# ethernet_chip_board.net
KiCad netlist of a schematic drawn in EAGLE
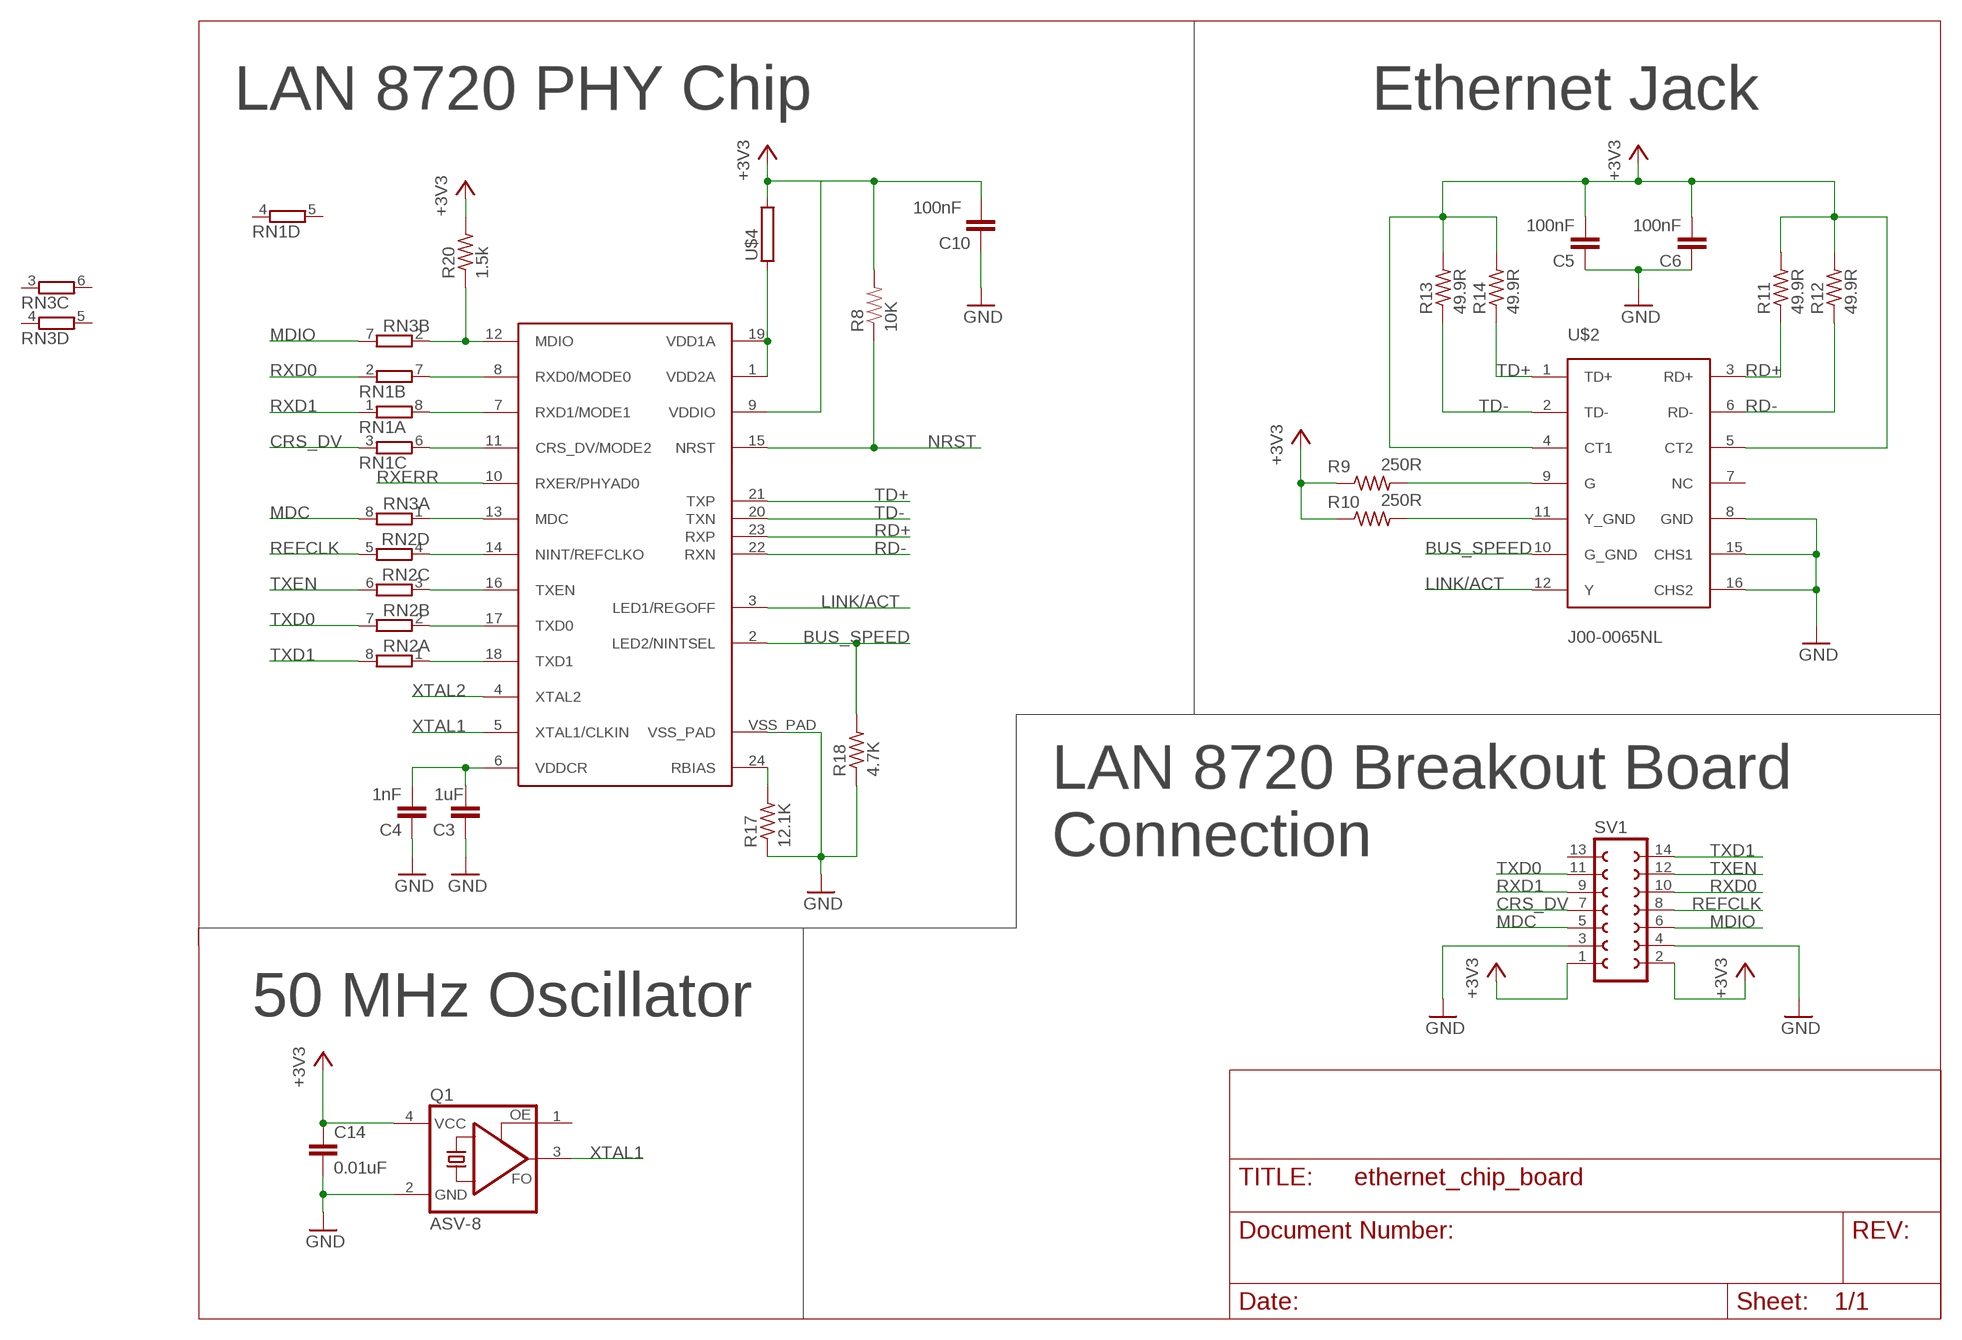
[diagram p0: schematic, sheet 1]

(export (version "E")
  (design (tool "Eeschema 10.0.6"))
  (components
    (comp (ref "C3")
      (value "1uF")
      (footprint "eagle-import:C0603")
      (libsource (lib "eagle-import") (part "CC0603"))
    )
    (comp (ref "C4")
      (value "1nF")
      (footprint "eagle-import:C0603")
      (libsource (lib "eagle-import") (part "CC0603"))
    )
    (comp (ref "C5")
      (value "100nF")
      (footprint "eagle-import:C0603")
      (libsource (lib "eagle-import") (part "CC0603"))
    )
    (comp (ref "C6")
      (value "100nF")
      (footprint "eagle-import:C0603")
      (libsource (lib "eagle-import") (part "CC0603"))
    )
    (comp (ref "C10")
      (value "100nF")
      (footprint "eagle-import:C0603")
      (libsource (lib "eagle-import") (part "CC0603"))
    )
    (comp (ref "C14")
      (value "0.01uF")
      (footprint "eagle-import:C0603")
      (libsource (lib "eagle-import") (part "C-EUC0603"))
    )
    (comp (ref "Q1")
      (value "ASV-8")
      (footprint "eagle-import:ASF")
      (libsource (lib "eagle-import") (part "ASF"))
    )
    (comp (ref "R8")
      (value "10K")
      (footprint "eagle-import:0603-RES")
      (libsource (lib "eagle-import") (part "RESISTOR0603-RES"))
    )
    (comp (ref "R9")
      (value "250R")
      (footprint "eagle-import:R0603")
      (libsource (lib "eagle-import") (part "R-US_R0603"))
    )
    (comp (ref "R10")
      (value "250R")
      (footprint "eagle-import:R0603")
      (libsource (lib "eagle-import") (part "R-US_R0603"))
    )
    (comp (ref "R11")
      (value "49.9R")
      (footprint "eagle-import:R0603")
      (libsource (lib "eagle-import") (part "R-US_R0603"))
    )
    (comp (ref "R12")
      (value "49.9R")
      (footprint "eagle-import:R0603")
      (libsource (lib "eagle-import") (part "R-US_R0603"))
    )
    (comp (ref "R13")
      (value "49.9R")
      (footprint "eagle-import:R0603")
      (libsource (lib "eagle-import") (part "R-US_R0603"))
    )
    (comp (ref "R14")
      (value "49.9R")
      (footprint "eagle-import:R0603")
      (libsource (lib "eagle-import") (part "R-US_R0603"))
    )
    (comp (ref "R17")
      (value "12.1K")
      (footprint "eagle-import:R0603")
      (libsource (lib "eagle-import") (part "R-US_R0603"))
    )
    (comp (ref "R18")
      (value "4.7K")
      (footprint "eagle-import:R0603")
      (libsource (lib "eagle-import") (part "R-US_R0603"))
    )
    (comp (ref "R20")
      (value "1.5k")
      (footprint "eagle-import:R0603")
      (libsource (lib "eagle-import") (part "R-US_R0603"))
    )
    (comp (ref "RN1")
      (value "4R-NCAY16")
      (footprint "eagle-import:CAY16")
      (libsource (lib "eagle-import") (part "4R-NCAY16"))
    )
    (comp (ref "RN2")
      (value "4R-NCAY16")
      (footprint "eagle-import:CAY16")
      (libsource (lib "eagle-import") (part "4R-NCAY16"))
    )
    (comp (ref "RN3")
      (value "4R-NCAY16")
      (footprint "eagle-import:CAY16")
      (libsource (lib "eagle-import") (part "4R-NCAY16"))
    )
    (comp (ref "SV1")
      (value "FE07-2")
      (footprint "eagle-import:FE07-2")
      (libsource (lib "eagle-import") (part "FE07-2"))
    )
    (comp (ref "U$1")
      (value "LAN8720LAN8720")
      (footprint "eagle-import:24-QFN")
      (libsource (lib "eagle-import") (part "LAN8720LAN8720"))
    )
    (comp (ref "U$2")
      (value "J00-0065NL")
      (footprint "eagle-import:J00-0065NL")
      (libsource (lib "eagle-import") (part "J00-0065NL"))
    )
    (comp (ref "U$4")
      (value "553-2382-1-ND")
      (footprint "eagle-import:0603")
      (libsource (lib "eagle-import") (part "553-2382-1-ND"))
    )
  )
  (nets
    (net (code "1") (name "+3V3") (class "Default")
      (node (ref "C10") (pin "2") (pinfunction "2_2") (pintype "passive"))
      (node (ref "C14") (pin "1") (pinfunction "1_1") (pintype "passive"))
      (node (ref "C5") (pin "2") (pinfunction "2_2") (pintype "passive"))
      (node (ref "C6") (pin "2") (pinfunction "2_2") (pintype "passive"))
      (node (ref "Q1") (pin "4") (pinfunction "VCC_4") (pintype "power_in"))
      (node (ref "R10") (pin "1") (pinfunction "1_1") (pintype "passive"))
      (node (ref "R11") (pin "2") (pinfunction "2_2") (pintype "passive"))
      (node (ref "R12") (pin "2") (pinfunction "2_2") (pintype "passive"))
      (node (ref "R13") (pin "2") (pinfunction "2_2") (pintype "passive"))
      (node (ref "R14") (pin "2") (pinfunction "2_2") (pintype "passive"))
      (node (ref "R20") (pin "2") (pinfunction "2_2") (pintype "passive"))
      (node (ref "R8") (pin "2") (pinfunction "2_2") (pintype "passive"))
      (node (ref "R9") (pin "1") (pinfunction "1_1") (pintype "passive"))
      (node (ref "SV1") (pin "1") (pinfunction "1_1") (pintype "passive"))
      (node (ref "SV1") (pin "2") (pinfunction "2_2") (pintype "passive"))
      (node (ref "U$1") (pin "9") (pinfunction "VDDIO_9") (pintype "bidirectional"))
      (node (ref "U$2") (pin "4") (pinfunction "CT1_4") (pintype "bidirectional"))
      (node (ref "U$2") (pin "5") (pinfunction "CT2_5") (pintype "bidirectional"))
      (node (ref "U$4") (pin "2") (pinfunction "2_2") (pintype "passive"))
    )
    (net (code "2") (name "/BUS_SPEED") (class "Default")
      (node (ref "R18") (pin "2") (pinfunction "2_2") (pintype "passive"))
      (node (ref "U$1") (pin "2") (pinfunction "LED2/NINTSEL_2") (pintype "bidirectional"))
      (node (ref "U$2") (pin "10") (pinfunction "G_GND_10") (pintype "bidirectional"))
    )
    (net (code "3") (name "/CRS_DV") (class "Default")
      (node (ref "RN1") (pin "3") (pinfunction "1_3") (pintype "passive"))
      (node (ref "SV1") (pin "7") (pinfunction "7_7") (pintype "passive"))
    )
    (net (code "4") (name "/LINK{slash}ACT") (class "Default")
      (node (ref "U$1") (pin "3") (pinfunction "LED1/REGOFF_3") (pintype "bidirectional"))
      (node (ref "U$2") (pin "12") (pinfunction "Y_12") (pintype "bidirectional"))
    )
    (net (code "5") (name "/MDC") (class "Default")
      (node (ref "RN3") (pin "8") (pinfunction "2_8") (pintype "passive"))
      (node (ref "SV1") (pin "5") (pinfunction "5_5") (pintype "passive"))
    )
    (net (code "6") (name "/MDIO") (class "Default")
      (node (ref "RN3") (pin "7") (pinfunction "2_7") (pintype "passive"))
      (node (ref "SV1") (pin "6") (pinfunction "6_6") (pintype "passive"))
    )
    (net (code "7") (name "/NRST") (class "Default")
      (node (ref "R8") (pin "1") (pinfunction "1_1") (pintype "passive"))
      (node (ref "U$1") (pin "15") (pinfunction "NRST_15") (pintype "bidirectional"))
    )
    (net (code "8") (name "/RD+") (class "Default")
      (node (ref "R11") (pin "1") (pinfunction "1_1") (pintype "passive"))
      (node (ref "U$1") (pin "23") (pinfunction "RXP_23") (pintype "bidirectional"))
      (node (ref "U$2") (pin "3") (pinfunction "RD+_3") (pintype "bidirectional"))
    )
    (net (code "9") (name "/RD-") (class "Default")
      (node (ref "R12") (pin "1") (pinfunction "1_1") (pintype "passive"))
      (node (ref "U$1") (pin "22") (pinfunction "RXN_22") (pintype "bidirectional"))
      (node (ref "U$2") (pin "6") (pinfunction "RD-_6") (pintype "bidirectional"))
    )
    (net (code "10") (name "/REFCLK") (class "Default")
      (node (ref "RN2") (pin "5") (pinfunction "2_5") (pintype "passive"))
      (node (ref "SV1") (pin "8") (pinfunction "8_8") (pintype "passive"))
    )
    (net (code "11") (name "/RXD0") (class "Default")
      (node (ref "RN1") (pin "2") (pinfunction "1_2") (pintype "passive"))
      (node (ref "SV1") (pin "10") (pinfunction "10_10") (pintype "passive"))
    )
    (net (code "12") (name "/RXD1") (class "Default")
      (node (ref "RN1") (pin "1") (pinfunction "1_1") (pintype "passive"))
      (node (ref "SV1") (pin "9") (pinfunction "9_9") (pintype "passive"))
    )
    (net (code "13") (name "/RXERR") (class "Default")
      (node (ref "U$1") (pin "10") (pinfunction "RXER/PHYAD0_10") (pintype "bidirectional"))
    )
    (net (code "14") (name "/TD+") (class "Default")
      (node (ref "R14") (pin "1") (pinfunction "1_1") (pintype "passive"))
      (node (ref "U$1") (pin "21") (pinfunction "TXP_21") (pintype "bidirectional"))
      (node (ref "U$2") (pin "1") (pinfunction "TD+_1") (pintype "bidirectional"))
    )
    (net (code "15") (name "/TD-") (class "Default")
      (node (ref "R13") (pin "1") (pinfunction "1_1") (pintype "passive"))
      (node (ref "U$1") (pin "20") (pinfunction "TXN_20") (pintype "bidirectional"))
      (node (ref "U$2") (pin "2") (pinfunction "TD-_2") (pintype "bidirectional"))
    )
    (net (code "16") (name "/TXD0") (class "Default")
      (node (ref "RN2") (pin "7") (pinfunction "2_7") (pintype "passive"))
      (node (ref "SV1") (pin "11") (pinfunction "11_11") (pintype "passive"))
    )
    (net (code "17") (name "/TXD1") (class "Default")
      (node (ref "RN2") (pin "8") (pinfunction "2_8") (pintype "passive"))
      (node (ref "SV1") (pin "14") (pinfunction "14_14") (pintype "passive"))
    )
    (net (code "18") (name "/TXEN") (class "Default")
      (node (ref "RN2") (pin "6") (pinfunction "2_6") (pintype "passive"))
      (node (ref "SV1") (pin "12") (pinfunction "12_12") (pintype "passive"))
    )
    (net (code "19") (name "/XTAL1") (class "Default")
      (node (ref "Q1") (pin "3") (pinfunction "FO_3") (pintype "output"))
      (node (ref "U$1") (pin "5") (pinfunction "XTAL1/CLKIN_5") (pintype "bidirectional"))
    )
    (net (code "20") (name "/XTAL2") (class "Default")
      (node (ref "U$1") (pin "4") (pinfunction "XTAL2_4") (pintype "bidirectional"))
    )
    (net (code "21") (name "GND") (class "Default")
      (node (ref "C10") (pin "1") (pinfunction "1_1") (pintype "passive"))
      (node (ref "C14") (pin "2") (pinfunction "2_2") (pintype "passive"))
      (node (ref "C3") (pin "1") (pinfunction "1_1") (pintype "passive"))
      (node (ref "C4") (pin "1") (pinfunction "1_1") (pintype "passive"))
      (node (ref "C5") (pin "1") (pinfunction "1_1") (pintype "passive"))
      (node (ref "C6") (pin "1") (pinfunction "1_1") (pintype "passive"))
      (node (ref "Q1") (pin "2") (pinfunction "GND_2") (pintype "power_in"))
      (node (ref "R17") (pin "1") (pinfunction "1_1") (pintype "passive"))
      (node (ref "R18") (pin "1") (pinfunction "1_1") (pintype "passive"))
      (node (ref "SV1") (pin "3") (pinfunction "3_3") (pintype "passive"))
      (node (ref "SV1") (pin "4") (pinfunction "4_4") (pintype "passive"))
      (node (ref "U$1") (pin "VSS_PAD") (pinfunction "VSS_PAD_VSS_PAD") (pintype "bidirectional"))
      (node (ref "U$2") (pin "15") (pinfunction "CHS1_15") (pintype "bidirectional"))
      (node (ref "U$2") (pin "16") (pinfunction "CHS2_16") (pintype "bidirectional"))
      (node (ref "U$2") (pin "8") (pinfunction "GND_8") (pintype "bidirectional"))
    )
    (net (code "22") (name "Net-(RN1A-2)") (class "Default")
      (node (ref "RN1") (pin "8") (pinfunction "2_8") (pintype "passive"))
      (node (ref "U$1") (pin "7") (pinfunction "RXD1/MODE1_7") (pintype "bidirectional"))
    )
    (net (code "23") (name "Net-(RN1B-2)") (class "Default")
      (node (ref "RN1") (pin "7") (pinfunction "2_7") (pintype "passive"))
      (node (ref "U$1") (pin "8") (pinfunction "RXD0/MODE0_8") (pintype "bidirectional"))
    )
    (net (code "24") (name "Net-(RN1C-2)") (class "Default")
      (node (ref "RN1") (pin "6") (pinfunction "2_6") (pintype "passive"))
      (node (ref "U$1") (pin "11") (pinfunction "CRS_DV/MODE2_11") (pintype "bidirectional"))
    )
    (net (code "25") (name "Net-(RN2B-1)") (class "Default")
      (node (ref "RN2") (pin "2") (pinfunction "1_2") (pintype "passive"))
      (node (ref "U$1") (pin "17") (pinfunction "TXD0_17") (pintype "bidirectional"))
    )
    (net (code "26") (name "Net-(RN2C-1)") (class "Default")
      (node (ref "RN2") (pin "3") (pinfunction "1_3") (pintype "passive"))
      (node (ref "U$1") (pin "16") (pinfunction "TXEN_16") (pintype "bidirectional"))
    )
    (net (code "27") (name "Net-(RN2D-1)") (class "Default")
      (node (ref "RN2") (pin "4") (pinfunction "1_4") (pintype "passive"))
      (node (ref "U$1") (pin "14") (pinfunction "NINT/REFCLKO_14") (pintype "bidirectional"))
    )
    (net (code "28") (name "Net-(RN3B-1)") (class "Default")
      (node (ref "R20") (pin "1") (pinfunction "1_1") (pintype "passive"))
      (node (ref "RN3") (pin "2") (pinfunction "1_2") (pintype "passive"))
      (node (ref "U$1") (pin "12") (pinfunction "MDIO_12") (pintype "bidirectional"))
    )
    (net (code "29") (name "Net-(U$1-MDC)") (class "Default")
      (node (ref "RN3") (pin "1") (pinfunction "1_1") (pintype "passive"))
      (node (ref "U$1") (pin "13") (pinfunction "MDC_13") (pintype "bidirectional"))
    )
    (net (code "30") (name "Net-(U$1-RBIAS)") (class "Default")
      (node (ref "R17") (pin "2") (pinfunction "2_2") (pintype "passive"))
      (node (ref "U$1") (pin "24") (pinfunction "RBIAS_24") (pintype "bidirectional"))
    )
    (net (code "31") (name "Net-(U$1-TXD1)") (class "Default")
      (node (ref "RN2") (pin "1") (pinfunction "1_1") (pintype "passive"))
      (node (ref "U$1") (pin "18") (pinfunction "TXD1_18") (pintype "bidirectional"))
    )
    (net (code "32") (name "Net-(U$1-VDD1A)") (class "Default")
      (node (ref "U$1") (pin "1") (pinfunction "VDD2A_1") (pintype "bidirectional"))
      (node (ref "U$1") (pin "19") (pinfunction "VDD1A_19") (pintype "bidirectional"))
      (node (ref "U$4") (pin "1") (pinfunction "1_1") (pintype "passive"))
    )
    (net (code "33") (name "Net-(U$1-VDDCR)") (class "Default")
      (node (ref "C3") (pin "2") (pinfunction "2_2") (pintype "passive"))
      (node (ref "C4") (pin "2") (pinfunction "2_2") (pintype "passive"))
      (node (ref "U$1") (pin "6") (pinfunction "VDDCR_6") (pintype "bidirectional"))
    )
    (net (code "34") (name "Net-(U$2-G)") (class "Default")
      (node (ref "R9") (pin "2") (pinfunction "2_2") (pintype "passive"))
      (node (ref "U$2") (pin "9") (pinfunction "G_9") (pintype "bidirectional"))
    )
    (net (code "35") (name "Net-(U$2-Y_GND)") (class "Default")
      (node (ref "R10") (pin "2") (pinfunction "2_2") (pintype "passive"))
      (node (ref "U$2") (pin "11") (pinfunction "Y_GND_11") (pintype "bidirectional"))
    )
    (net (code "36") (name "unconnected-(Q1-OE-Pad1)") (class "Default")
      (node (ref "Q1") (pin "1") (pinfunction "OE_1") (pintype "input"))
    )
    (net (code "37") (name "unconnected-(RN1D-1-Pad4)") (class "Default")
      (node (ref "RN1") (pin "4") (pinfunction "1_4") (pintype "passive"))
    )
    (net (code "38") (name "unconnected-(RN1D-2-Pad5)") (class "Default")
      (node (ref "RN1") (pin "5") (pinfunction "2_5") (pintype "passive"))
    )
    (net (code "39") (name "unconnected-(RN3C-1-Pad3)") (class "Default")
      (node (ref "RN3") (pin "3") (pinfunction "1_3") (pintype "passive"))
    )
    (net (code "40") (name "unconnected-(RN3C-2-Pad6)") (class "Default")
      (node (ref "RN3") (pin "6") (pinfunction "2_6") (pintype "passive"))
    )
    (net (code "41") (name "unconnected-(RN3D-1-Pad4)") (class "Default")
      (node (ref "RN3") (pin "4") (pinfunction "1_4") (pintype "passive"))
    )
    (net (code "42") (name "unconnected-(RN3D-2-Pad5)") (class "Default")
      (node (ref "RN3") (pin "5") (pinfunction "2_5") (pintype "passive"))
    )
    (net (code "43") (name "unconnected-(SV1-Pad13)") (class "Default")
      (node (ref "SV1") (pin "13") (pinfunction "13_13") (pintype "passive"))
    )
    (net (code "44") (name "unconnected-(U$2-NC-Pad7)") (class "Default")
      (node (ref "U$2") (pin "7") (pinfunction "NC_7") (pintype "bidirectional"))
    )
  )
)
